# SCH_campfire-hackercard_2026-01-01.net
KiCad netlist of a schematic drawn in EasyEDA
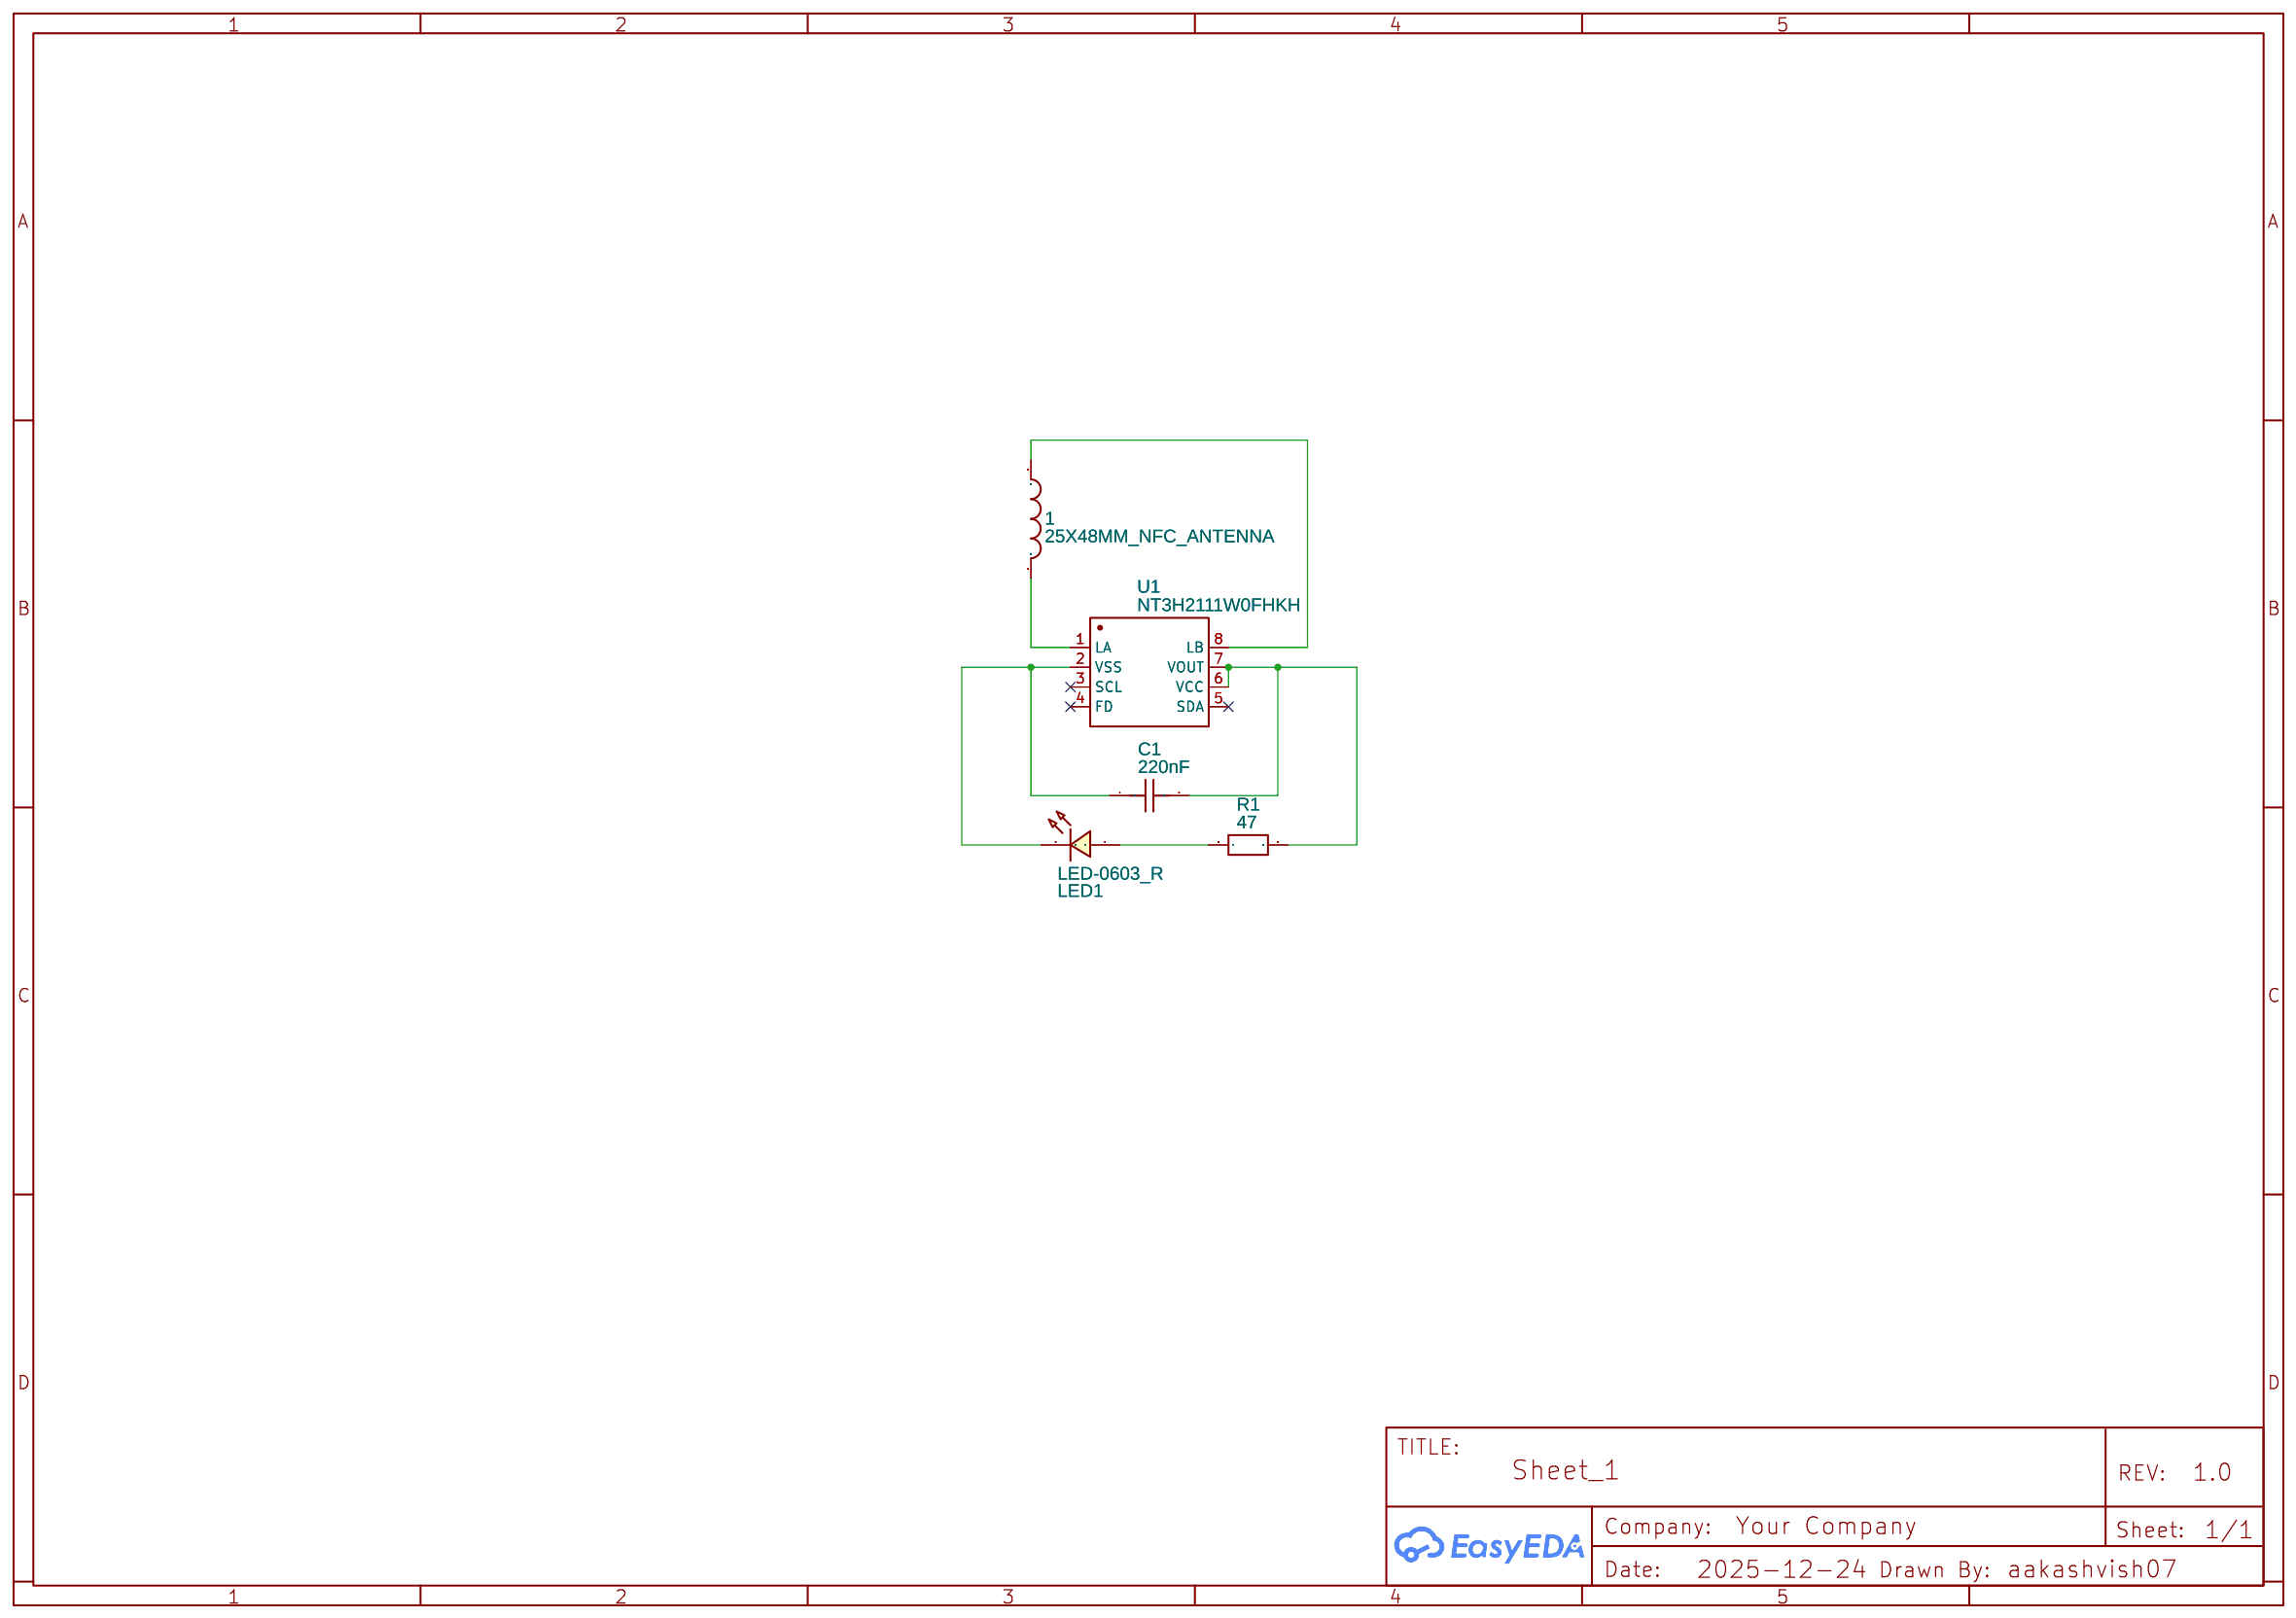
[diagram p0: schematic sheet]

(export (version "E")
  (design (tool "Eeschema 10.0.6"))
  (components
    (comp (ref "1") (value "25X48MM_NFC_ANTENNA") (libsource (lib "") (part "25X48MM_NFC_ANTENNA")))
    (comp (ref "C1") (value "220nF") (libsource (lib "") (part "C_0603_US")))
    (comp (ref "LED1")
      (value "LED-0603_R")
      (fields
        (field (name "Manufacturer Part") "19-217/R6C-AL1M2VY/3T")
        (field (name "Manufacturer") "EVERLIGHT(台湾亿光)")
      )
      (libsource (lib "") (part "LED-0603_R"))
    )
    (comp (ref "R1") (value "47") (libsource (lib "") (part "R_0603_EU")))
    (comp (ref "U1")
      (value "NT3H2111W0FHKH")
      (fields (field (name "Manufacturer") "NXP(恩智浦)"))
      (libsource (lib "") (part "NT3H2111W0FHKH"))
    )
  )
  (nets
    (net (code "1") (name "Net-(LED1-Pad1)") (class "Default")
      (node (ref "LED1") (pin "1") (pinfunction "1_1") (pintype "unspecified"))
      (node (ref "R1") (pin "1") (pinfunction "1_1") (pintype "unspecified"))
    )
    (net (code "2") (name "Net-(U1-LA)") (class "Default")
      (node (ref "1") (pin "P$2") (pinfunction "P$2_P$2") (pintype "bidirectional"))
      (node (ref "U1") (pin "1") (pinfunction "LA_1") (pintype "unspecified"))
    )
    (net (code "3") (name "Net-(U1-LB)") (class "Default")
      (node (ref "1") (pin "P$1") (pinfunction "P$1_P$1") (pintype "bidirectional"))
      (node (ref "U1") (pin "8") (pinfunction "LB_8") (pintype "unspecified"))
    )
    (net (code "4") (name "Net-(U1-VCC)") (class "Default")
      (node (ref "C1") (pin "2") (pinfunction "2_2") (pintype "unspecified"))
      (node (ref "R1") (pin "2") (pinfunction "2_2") (pintype "unspecified"))
      (node (ref "U1") (pin "6") (pinfunction "VCC_6") (pintype "unspecified"))
      (node (ref "U1") (pin "7") (pinfunction "VOUT_7") (pintype "unspecified"))
    )
    (net (code "5") (name "Net-(U1-VSS)") (class "Default")
      (node (ref "C1") (pin "1") (pinfunction "1_1") (pintype "unspecified"))
      (node (ref "LED1") (pin "2") (pinfunction "2_2") (pintype "unspecified"))
      (node (ref "U1") (pin "2") (pinfunction "VSS_2") (pintype "unspecified"))
    )
    (net (code "6") (name "unconnected-(U1-FD-Pad4)") (class "Default")
      (node (ref "U1") (pin "4") (pinfunction "FD_4") (pintype "unspecified+no_connect"))
    )
    (net (code "7") (name "unconnected-(U1-SCL-Pad3)") (class "Default")
      (node (ref "U1") (pin "3") (pinfunction "SCL_3") (pintype "unspecified+no_connect"))
    )
    (net (code "8") (name "unconnected-(U1-SDA-Pad5)") (class "Default")
      (node (ref "U1") (pin "5") (pinfunction "SDA_5") (pintype "unspecified+no_connect"))
    )
  )
)
